# Sheet1.net
KiCad netlist of a schematic drawn in Altium Designer
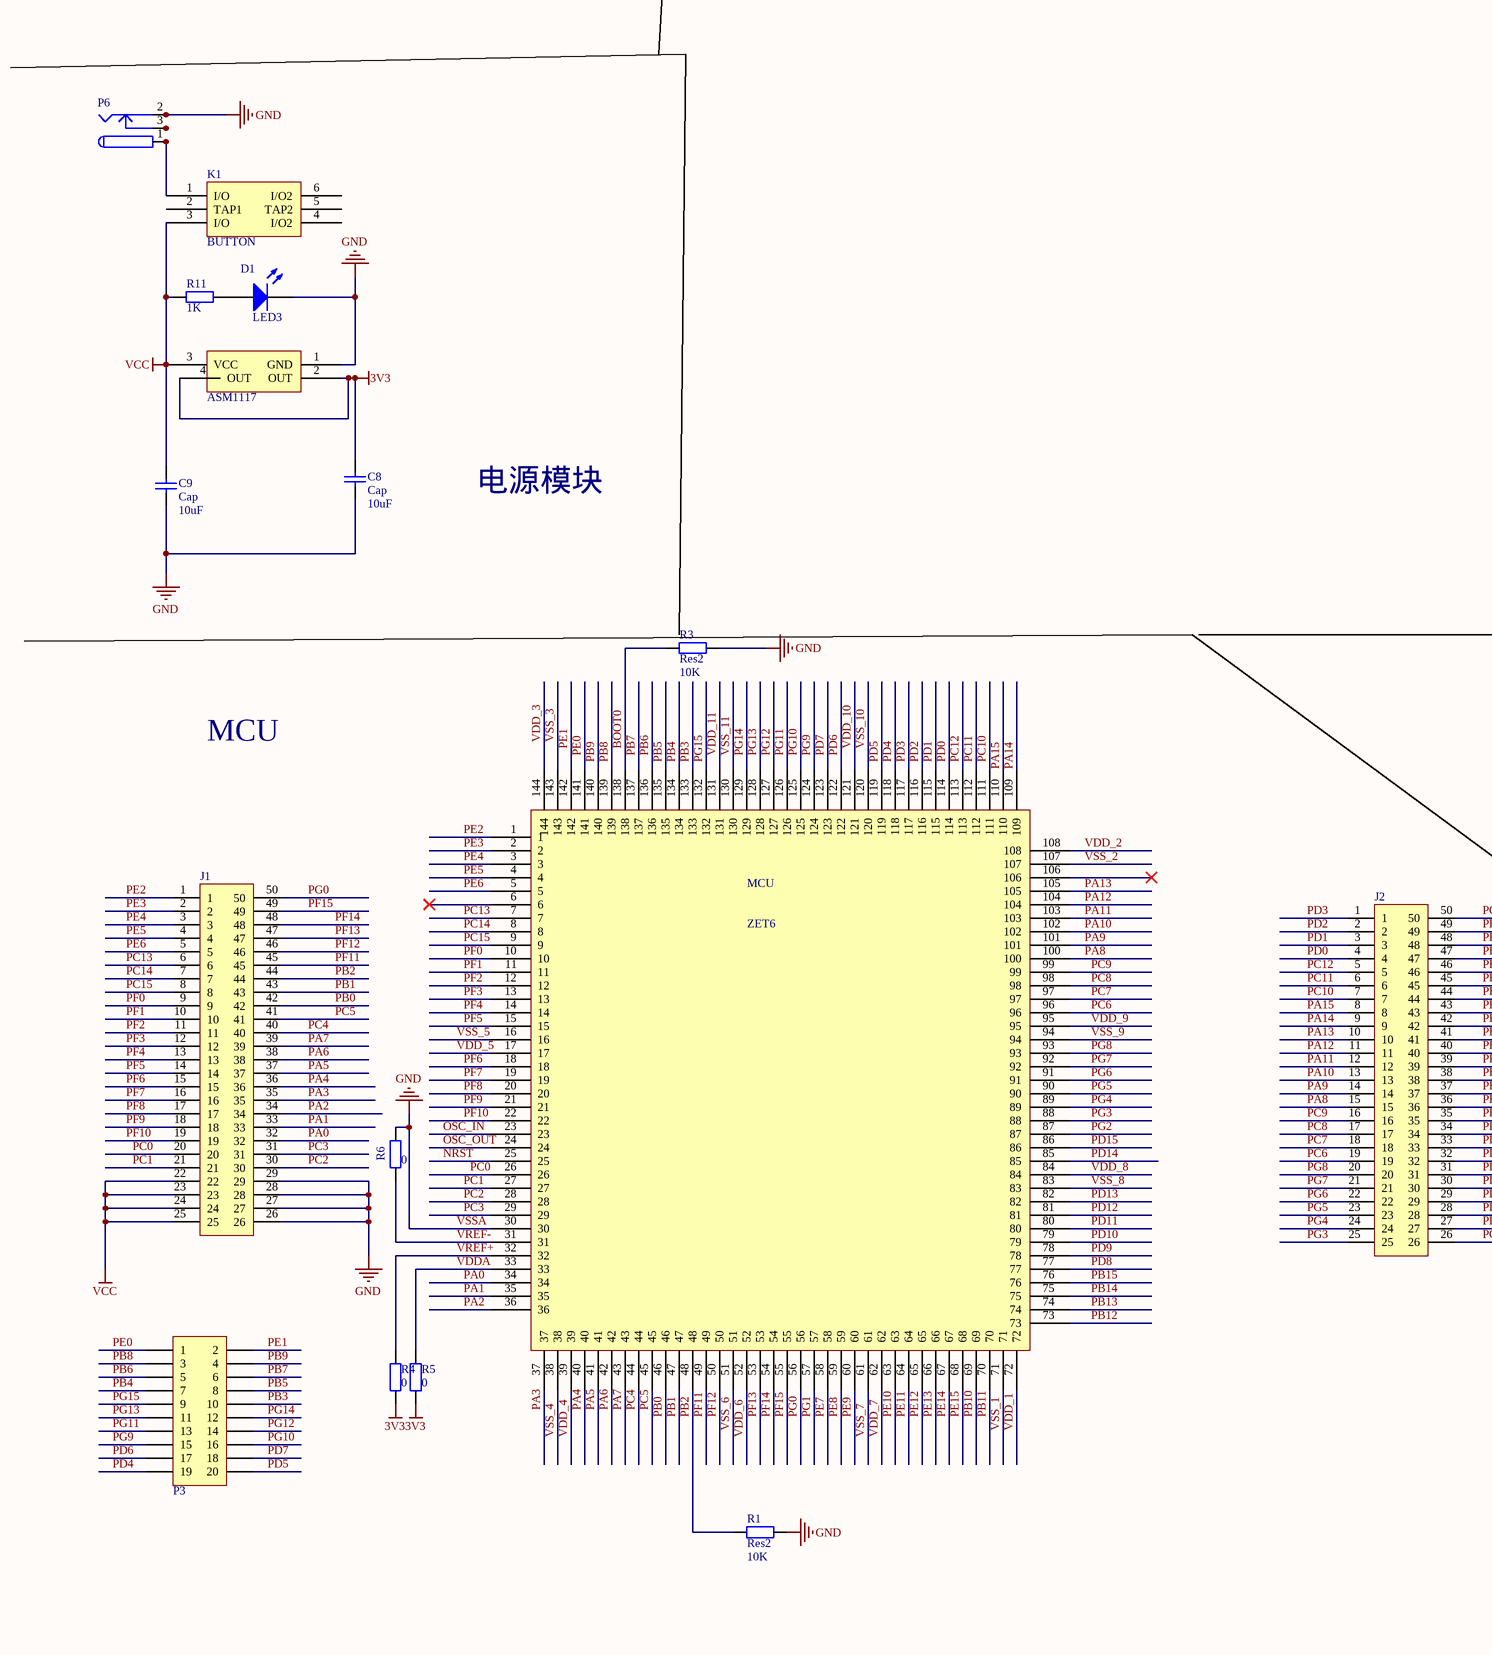
[diagram p0: Sheet1.SchDoc, left]
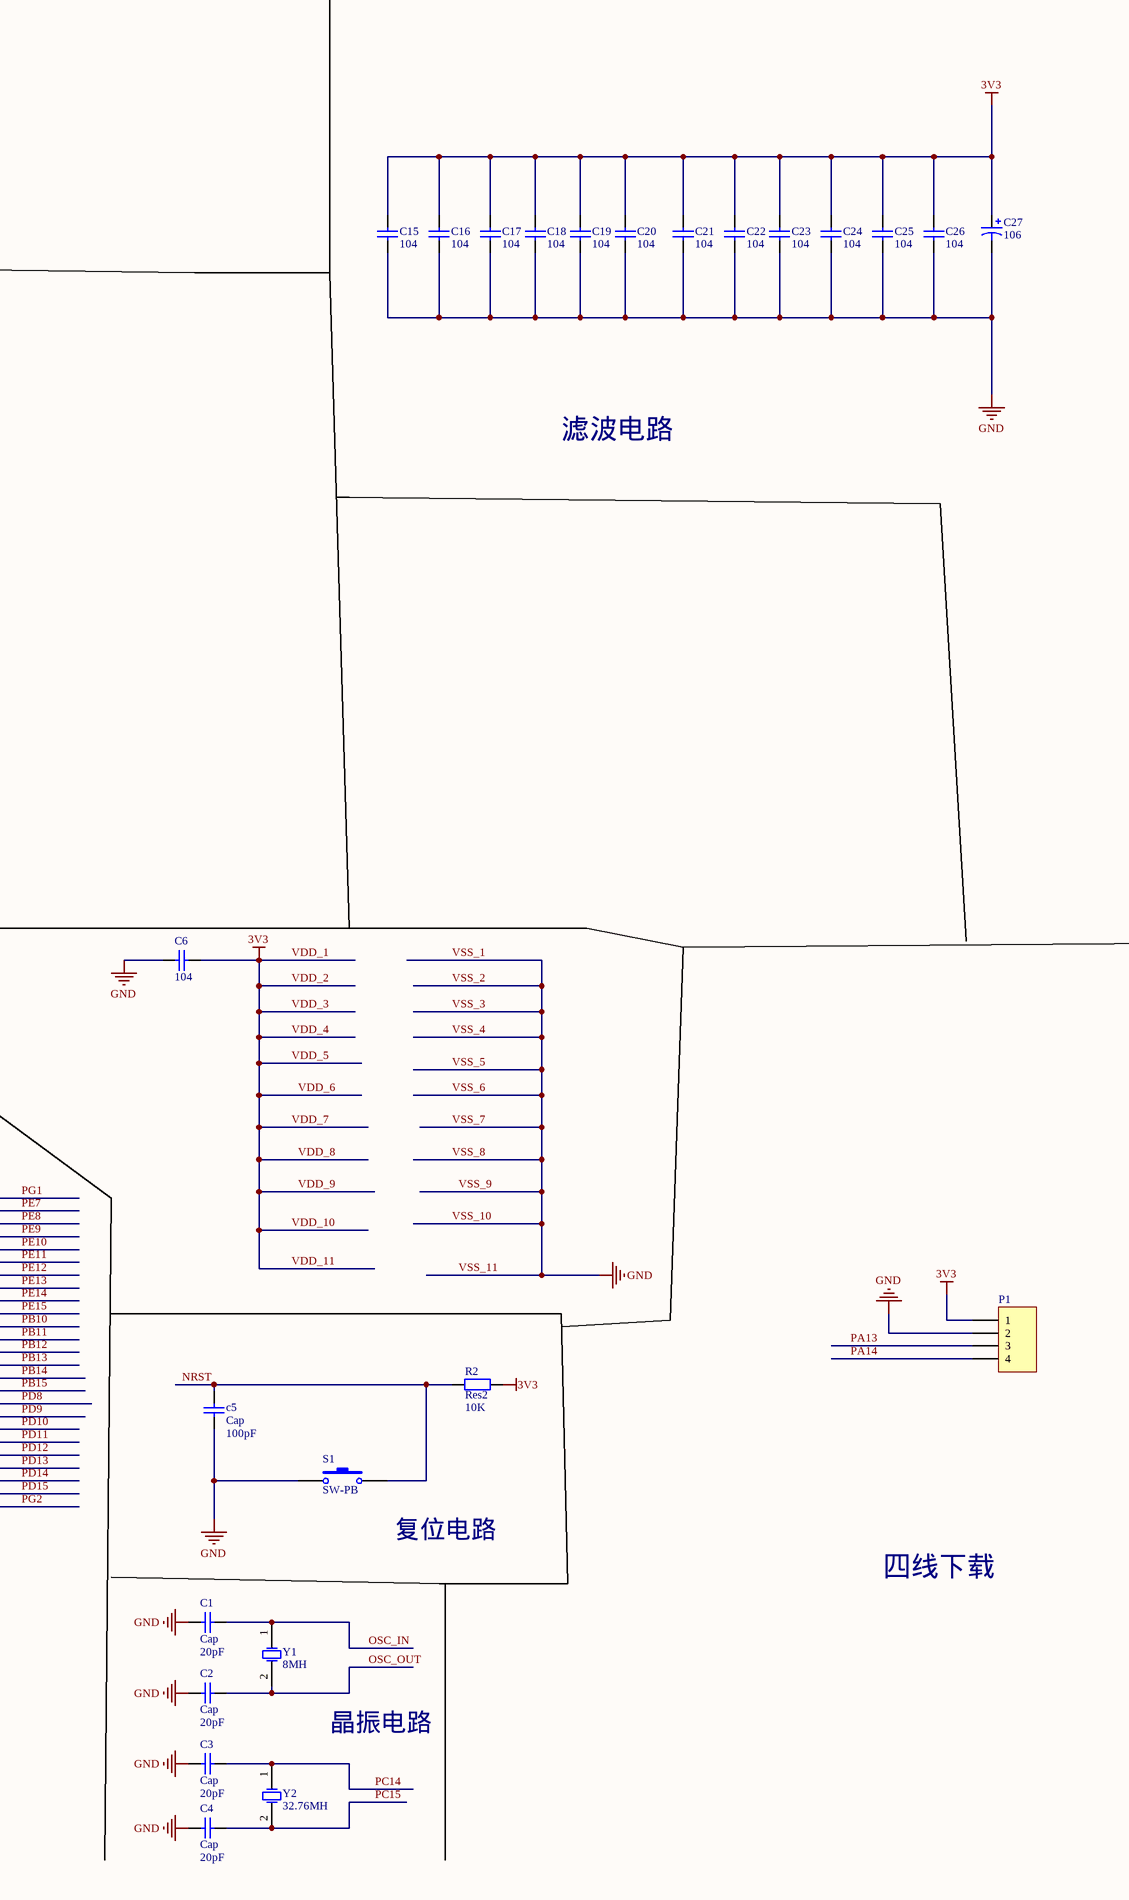
[diagram p1: Sheet1.SchDoc, right]

(export (version "E")
  (design (tool "Eeschema 10.0.6"))
  (components
    (comp (ref "*") (value "ASM1117") (footprint "AMS1117") (libsource (lib "Schlib1") (part "ASM1117")))
    (comp (ref "C1")
      (value "Cap")
      (footprint "0805")
      (description "Capacitor")
      (fields (field (name "ALTIUM_VALUE") "20pF") (field (name "PUBLISHER") "Altium Limited"))
      (libsource (lib "Miscellaneous Devices") (part "Cap"))
    )
    (comp (ref "C2")
      (value "Cap")
      (footprint "0805")
      (description "Capacitor")
      (fields (field (name "ALTIUM_VALUE") "20pF") (field (name "PUBLISHER") "Altium Limited"))
      (libsource (lib "Miscellaneous Devices") (part "Cap"))
    )
    (comp (ref "C3")
      (value "Cap")
      (footprint "0805")
      (description "Capacitor")
      (fields (field (name "ALTIUM_VALUE") "20pF") (field (name "PUBLISHER") "Altium Limited"))
      (libsource (lib "Miscellaneous Devices") (part "Cap"))
    )
    (comp (ref "C4")
      (value "Cap")
      (footprint "0805")
      (description "Capacitor")
      (fields (field (name "ALTIUM_VALUE") "20pF") (field (name "PUBLISHER") "Altium Limited"))
      (libsource (lib "Miscellaneous Devices") (part "Cap"))
    )
    (comp (ref "c5")
      (value "Cap")
      (footprint "0805")
      (description "Capacitor")
      (fields (field (name "ALTIUM_VALUE") "100pF") (field (name "PUBLISHER") "Altium Limited"))
      (libsource (lib "Miscellaneous Devices") (part "Cap"))
    )
    (comp (ref "C6")
      (value "104")
      (footprint "0805")
      (description "Capacitor (Semiconductor SIM Model)")
      (fields (field (name "Comment") "Cap Semi") (field (name "PUBLISHER") "Altium Limited"))
      (libsource (lib "Miscellaneous Devices") (part "Cap Semi"))
    )
    (comp (ref "C8")
      (value "Cap")
      (footprint "0805")
      (description "Capacitor")
      (fields (field (name "ALTIUM_VALUE") "10uF") (field (name "PUBLISHER") "Altium Limited"))
      (libsource (lib "Miscellaneous Devices") (part "Cap"))
    )
    (comp (ref "C9")
      (value "Cap")
      (footprint "0805")
      (description "Capacitor")
      (fields (field (name "ALTIUM_VALUE") "10uF") (field (name "PUBLISHER") "Altium Limited"))
      (libsource (lib "Miscellaneous Devices") (part "Cap"))
    )
    (comp (ref "C15")
      (value "104")
      (footprint "0805")
      (description "Capacitor")
      (fields (field (name "Comment") "Cap") (field (name "PUBLISHER") "Altium Limited"))
      (libsource (lib "Miscellaneous Devices") (part "Cap"))
    )
    (comp (ref "C16")
      (value "104")
      (footprint "0805")
      (description "Capacitor")
      (fields (field (name "Comment") "Cap") (field (name "PUBLISHER") "Altium Limited"))
      (libsource (lib "Miscellaneous Devices") (part "Cap"))
    )
    (comp (ref "C17")
      (value "104")
      (footprint "0805")
      (description "Capacitor")
      (fields (field (name "Comment") "Cap") (field (name "PUBLISHER") "Altium Limited"))
      (libsource (lib "Miscellaneous Devices") (part "Cap"))
    )
    (comp (ref "C18")
      (value "104")
      (footprint "0805")
      (description "Capacitor")
      (fields (field (name "Comment") "Cap") (field (name "PUBLISHER") "Altium Limited"))
      (libsource (lib "Miscellaneous Devices") (part "Cap"))
    )
    (comp (ref "C19")
      (value "104")
      (footprint "0805")
      (description "Capacitor")
      (fields (field (name "Comment") "Cap") (field (name "PUBLISHER") "Altium Limited"))
      (libsource (lib "Miscellaneous Devices") (part "Cap"))
    )
    (comp (ref "C20")
      (value "104")
      (footprint "0805")
      (description "Capacitor")
      (fields (field (name "Comment") "Cap") (field (name "PUBLISHER") "Altium Limited"))
      (libsource (lib "Miscellaneous Devices") (part "Cap"))
    )
    (comp (ref "C21")
      (value "104")
      (footprint "0805")
      (description "Capacitor")
      (fields (field (name "Comment") "Cap") (field (name "PUBLISHER") "Altium Limited"))
      (libsource (lib "Miscellaneous Devices") (part "Cap"))
    )
    (comp (ref "C22")
      (value "104")
      (footprint "0805")
      (description "Capacitor")
      (fields (field (name "Comment") "Cap") (field (name "PUBLISHER") "Altium Limited"))
      (libsource (lib "Miscellaneous Devices") (part "Cap"))
    )
    (comp (ref "C23")
      (value "104")
      (footprint "0805")
      (description "Capacitor")
      (fields (field (name "Comment") "Cap") (field (name "PUBLISHER") "Altium Limited"))
      (libsource (lib "Miscellaneous Devices") (part "Cap"))
    )
    (comp (ref "C24")
      (value "104")
      (footprint "0805")
      (description "Capacitor")
      (fields (field (name "Comment") "Cap") (field (name "PUBLISHER") "Altium Limited"))
      (libsource (lib "Miscellaneous Devices") (part "Cap"))
    )
    (comp (ref "C25")
      (value "104")
      (footprint "0805")
      (description "Capacitor")
      (fields (field (name "Comment") "Cap") (field (name "PUBLISHER") "Altium Limited"))
      (libsource (lib "Miscellaneous Devices") (part "Cap"))
    )
    (comp (ref "C26")
      (value "104")
      (footprint "0805")
      (description "Capacitor")
      (fields (field (name "Comment") "Cap") (field (name "PUBLISHER") "Altium Limited"))
      (libsource (lib "Miscellaneous Devices") (part "Cap"))
    )
    (comp (ref "C27")
      (value "106")
      (footprint "CC6.56.5")
      (description "Polarized Capacitor (Radial)")
      (fields (field (name "Comment") "Cap Pol1") (field (name "PUBLISHER") "Altium Limited"))
      (libsource (lib "Miscellaneous Devices") (part "Cap Pol1"))
    )
    (comp (ref "D1")
      (value "LED3")
      (footprint "RB.1")
      (description "Typical BLUE SiC LED")
      (fields (field (name "PUBLISHER") "Altium Limited"))
      (libsource (lib "Miscellaneous Devices") (part "LED3"))
    )
    (comp (ref "J1")
      (value "Edge Con 50")
      (footprint "HDR2X25")
      (description "50-Pin Edge Connector")
      (fields (field (name "PUBLISHER") "Altium Limited"))
      (libsource (lib "Miscellaneous Connectors") (part "Edge Con 50"))
    )
    (comp (ref "J2")
      (value "Edge Con 50")
      (footprint "HDR2X25")
      (description "50-Pin Edge Connector")
      (fields (field (name "PUBLISHER") "Altium Limited"))
      (libsource (lib "Miscellaneous Connectors") (part "Edge Con 50"))
    )
    (comp (ref "K1") (value "BUTTON") (footprint "BTN8.5*8.5") (libsource (lib "Schlib1") (part "BUTTON")))
    (comp (ref "P1")
      (value "Header 4")
      (footprint "HDR1X4")
      (description "Header, 4-Pin")
      (fields (field (name "PUBLISHER") "Altium Limited"))
      (libsource (lib "Miscellaneous Connectors") (part "Header 4"))
    )
    (comp (ref "P3")
      (value "Header 10X2H")
      (footprint "HDR2X10")
      (description "Header, 10-Pin, Dual row, Right Angle")
      (fields (field (name "PUBLISHER") "Altium Limited"))
      (libsource (lib "Miscellaneous Connectors") (part "Header 10X2H"))
    )
    (comp (ref "P6")
      (value "PWR2.5")
      (footprint "POWER_002")
      (description "Low Voltage Power Supply Connector")
      (fields (field (name "PUBLISHER") "Altium Limited"))
      (libsource (lib "Miscellaneous Connectors") (part "PWR2.5"))
    )
    (comp (ref "R1")
      (value "Res2")
      (footprint "0805")
      (description "Resistor")
      (fields (field (name "ALTIUM_VALUE") "10K") (field (name "PUBLISHER") "Altium Limited"))
      (libsource (lib "Miscellaneous Devices") (part "Res2"))
    )
    (comp (ref "R2")
      (value "Res2")
      (footprint "0805")
      (description "Resistor")
      (fields (field (name "ALTIUM_VALUE") "10K") (field (name "PUBLISHER") "Altium Limited"))
      (libsource (lib "Miscellaneous Devices") (part "Res2"))
    )
    (comp (ref "R3")
      (value "Res2")
      (footprint "0805")
      (description "Resistor")
      (fields (field (name "ALTIUM_VALUE") "10K") (field (name "PUBLISHER") "Altium Limited"))
      (libsource (lib "Miscellaneous Devices") (part "Res2"))
    )
    (comp (ref "R4")
      (value "0")
      (footprint "0805")
      (description "Resistor")
      (fields (field (name "Comment") "Res2") (field (name "PUBLISHER") "Altium Limited"))
      (libsource (lib "") (part "Res2_1"))
    )
    (comp (ref "R5")
      (value "0")
      (footprint "0805")
      (description "Resistor")
      (fields (field (name "Comment") "Res2") (field (name "PUBLISHER") "Altium Limited"))
      (libsource (lib "") (part "Res2_1"))
    )
    (comp (ref "R6")
      (value "0")
      (footprint "0805")
      (description "Resistor")
      (fields (field (name "Comment") "Res2") (field (name "PUBLISHER") "Altium Limited"))
      (libsource (lib "") (part "Res2_1"))
    )
    (comp (ref "R11")
      (value "1K")
      (footprint "0805")
      (description "Resistor")
      (fields (field (name "Comment") "Res2") (field (name "PUBLISHER") "Altium Limited"))
      (libsource (lib "Miscellaneous Devices") (part "Res2"))
    )
    (comp (ref "S1")
      (value "SW-PB")
      (footprint "key4")
      (description "Switch")
      (fields (field (name "PUBLISHER") "Altium Limited"))
      (libsource (lib "Miscellaneous Devices") (part "SW-PB"))
    )
    (comp (ref "Y1")
      (value "8MH")
      (footprint "XTAL_US")
      (description "Crystal Oscillator")
      (fields (field (name "PUBLISHER") "Altium Limited"))
      (libsource (lib "Miscellaneous Devices") (part "XTAL"))
    )
    (comp (ref "Y2")
      (value "32.76MH")
      (footprint "XTAL4")
      (description "Crystal Oscillator")
      (fields (field (name "PUBLISHER") "Altium Limited"))
      (libsource (lib "Miscellaneous Devices") (part "XTAL"))
    )
    (comp (ref "ZET6") (value "MCU") (footprint "LQFP144") (libsource (lib "Schlib1") (part "Component_1")))
  )
  (nets
    (net (code "1") (name "/BOOT0") (class "Default")
      (node (ref "R3") (pin "1") (pinfunction "1_1") (pintype "passive"))
      (node (ref "ZET6") (pin "138") (pinfunction "138_138") (pintype "passive"))
    )
    (net (code "2") (name "/NRST") (class "Default")
      (node (ref "R2") (pin "1") (pinfunction "1_1") (pintype "passive"))
      (node (ref "S1") (pin "2") (pinfunction "2_2") (pintype "passive"))
      (node (ref "ZET6") (pin "25") (pinfunction "25_25") (pintype "passive"))
      (node (ref "c5") (pin "2") (pinfunction "2_2") (pintype "passive"))
    )
    (net (code "3") (name "/OSC_IN") (class "Default")
      (node (ref "C1") (pin "2") (pinfunction "2_2") (pintype "passive"))
      (node (ref "Y1") (pin "1") (pinfunction "OSC1_1") (pintype "passive"))
      (node (ref "ZET6") (pin "23") (pinfunction "23_23") (pintype "passive"))
    )
    (net (code "4") (name "/OSC_OUT") (class "Default")
      (node (ref "C2") (pin "2") (pinfunction "2_2") (pintype "passive"))
      (node (ref "Y1") (pin "2") (pinfunction "OSC2_2") (pintype "passive"))
      (node (ref "ZET6") (pin "24") (pinfunction "24_24") (pintype "passive"))
    )
    (net (code "5") (name "/PA0") (class "Default")
      (node (ref "J1") (pin "32") (pinfunction "32_32") (pintype "passive"))
      (node (ref "ZET6") (pin "34") (pinfunction "34_34") (pintype "passive"))
    )
    (net (code "6") (name "/PA1") (class "Default")
      (node (ref "J1") (pin "33") (pinfunction "33_33") (pintype "passive"))
      (node (ref "ZET6") (pin "35") (pinfunction "35_35") (pintype "passive"))
    )
    (net (code "7") (name "/PA2") (class "Default")
      (node (ref "J1") (pin "34") (pinfunction "34_34") (pintype "passive"))
      (node (ref "ZET6") (pin "36") (pinfunction "36_36") (pintype "passive"))
    )
    (net (code "8") (name "/PA3") (class "Default")
      (node (ref "J1") (pin "35") (pinfunction "35_35") (pintype "passive"))
      (node (ref "ZET6") (pin "37") (pinfunction "37_37") (pintype "passive"))
    )
    (net (code "9") (name "/PA4") (class "Default")
      (node (ref "J1") (pin "36") (pinfunction "36_36") (pintype "passive"))
      (node (ref "ZET6") (pin "40") (pinfunction "40_40") (pintype "passive"))
    )
    (net (code "10") (name "/PA5") (class "Default")
      (node (ref "J1") (pin "37") (pinfunction "37_37") (pintype "passive"))
      (node (ref "ZET6") (pin "41") (pinfunction "41_41") (pintype "passive"))
    )
    (net (code "11") (name "/PA6") (class "Default")
      (node (ref "J1") (pin "38") (pinfunction "38_38") (pintype "passive"))
      (node (ref "ZET6") (pin "42") (pinfunction "42_42") (pintype "passive"))
    )
    (net (code "12") (name "/PA7") (class "Default")
      (node (ref "J1") (pin "39") (pinfunction "39_39") (pintype "passive"))
      (node (ref "ZET6") (pin "43") (pinfunction "43_43") (pintype "passive"))
    )
    (net (code "13") (name "/PA8") (class "Default")
      (node (ref "J2") (pin "15") (pinfunction "15_15") (pintype "passive"))
      (node (ref "ZET6") (pin "100") (pinfunction "100_100") (pintype "passive"))
    )
    (net (code "14") (name "/PA9") (class "Default")
      (node (ref "J2") (pin "14") (pinfunction "14_14") (pintype "passive"))
      (node (ref "ZET6") (pin "101") (pinfunction "101_101") (pintype "passive"))
    )
    (net (code "15") (name "/PA10") (class "Default")
      (node (ref "J2") (pin "13") (pinfunction "13_13") (pintype "passive"))
      (node (ref "ZET6") (pin "102") (pinfunction "102_102") (pintype "passive"))
    )
    (net (code "16") (name "/PA11") (class "Default")
      (node (ref "J2") (pin "12") (pinfunction "12_12") (pintype "passive"))
      (node (ref "ZET6") (pin "103") (pinfunction "103_103") (pintype "passive"))
    )
    (net (code "17") (name "/PA12") (class "Default")
      (node (ref "J2") (pin "11") (pinfunction "11_11") (pintype "passive"))
      (node (ref "ZET6") (pin "104") (pinfunction "104_104") (pintype "passive"))
    )
    (net (code "18") (name "/PA13") (class "Default")
      (node (ref "J2") (pin "10") (pinfunction "10_10") (pintype "passive"))
      (node (ref "P1") (pin "3") (pinfunction "3_3") (pintype "passive"))
      (node (ref "ZET6") (pin "105") (pinfunction "105_105") (pintype "passive"))
    )
    (net (code "19") (name "/PA14") (class "Default")
      (node (ref "J2") (pin "9") (pinfunction "9_9") (pintype "passive"))
      (node (ref "P1") (pin "4") (pinfunction "4_4") (pintype "passive"))
      (node (ref "ZET6") (pin "109") (pinfunction "109_109") (pintype "passive"))
    )
    (net (code "20") (name "/PA15") (class "Default")
      (node (ref "J2") (pin "8") (pinfunction "8_8") (pintype "passive"))
      (node (ref "ZET6") (pin "110") (pinfunction "110_110") (pintype "passive"))
    )
    (net (code "21") (name "/PB0") (class "Default")
      (node (ref "J1") (pin "42") (pinfunction "42_42") (pintype "passive"))
      (node (ref "ZET6") (pin "46") (pinfunction "46_46") (pintype "passive"))
    )
    (net (code "22") (name "/PB1") (class "Default")
      (node (ref "J1") (pin "43") (pinfunction "43_43") (pintype "passive"))
      (node (ref "ZET6") (pin "47") (pinfunction "47_47") (pintype "passive"))
    )
    (net (code "23") (name "/PB2") (class "Default")
      (node (ref "J1") (pin "44") (pinfunction "44_44") (pintype "passive"))
      (node (ref "R1") (pin "1") (pinfunction "1_1") (pintype "passive"))
      (node (ref "ZET6") (pin "48") (pinfunction "48_48") (pintype "passive"))
    )
    (net (code "24") (name "/PB3") (class "Default")
      (node (ref "P3") (pin "10") (pinfunction "10_10") (pintype "passive"))
      (node (ref "ZET6") (pin "133") (pinfunction "133_133") (pintype "passive"))
    )
    (net (code "25") (name "/PB4") (class "Default")
      (node (ref "P3") (pin "7") (pinfunction "7_7") (pintype "passive"))
      (node (ref "ZET6") (pin "134") (pinfunction "134_134") (pintype "passive"))
    )
    (net (code "26") (name "/PB5") (class "Default")
      (node (ref "P3") (pin "8") (pinfunction "8_8") (pintype "passive"))
      (node (ref "ZET6") (pin "135") (pinfunction "135_135") (pintype "passive"))
    )
    (net (code "27") (name "/PB6") (class "Default")
      (node (ref "P3") (pin "5") (pinfunction "5_5") (pintype "passive"))
      (node (ref "ZET6") (pin "136") (pinfunction "136_136") (pintype "passive"))
    )
    (net (code "28") (name "/PB7") (class "Default")
      (node (ref "P3") (pin "6") (pinfunction "6_6") (pintype "passive"))
      (node (ref "ZET6") (pin "137") (pinfunction "137_137") (pintype "passive"))
    )
    (net (code "29") (name "/PB8") (class "Default")
      (node (ref "P3") (pin "3") (pinfunction "3_3") (pintype "passive"))
      (node (ref "ZET6") (pin "139") (pinfunction "139_139") (pintype "passive"))
    )
    (net (code "30") (name "/PB9") (class "Default")
      (node (ref "P3") (pin "4") (pinfunction "4_4") (pintype "passive"))
      (node (ref "ZET6") (pin "140") (pinfunction "140_140") (pintype "passive"))
    )
    (net (code "31") (name "/PB10") (class "Default")
      (node (ref "J2") (pin "40") (pinfunction "40_40") (pintype "passive"))
      (node (ref "ZET6") (pin "69") (pinfunction "69_69") (pintype "passive"))
    )
    (net (code "32") (name "/PB11") (class "Default")
      (node (ref "J2") (pin "39") (pinfunction "39_39") (pintype "passive"))
      (node (ref "ZET6") (pin "70") (pinfunction "70_70") (pintype "passive"))
    )
    (net (code "33") (name "/PB12") (class "Default")
      (node (ref "J2") (pin "38") (pinfunction "38_38") (pintype "passive"))
      (node (ref "ZET6") (pin "73") (pinfunction "73_73") (pintype "passive"))
    )
    (net (code "34") (name "/PB13") (class "Default")
      (node (ref "J2") (pin "37") (pinfunction "37_37") (pintype "passive"))
      (node (ref "ZET6") (pin "74") (pinfunction "74_74") (pintype "passive"))
    )
    (net (code "35") (name "/PB14") (class "Default")
      (node (ref "J2") (pin "36") (pinfunction "36_36") (pintype "passive"))
      (node (ref "ZET6") (pin "75") (pinfunction "75_75") (pintype "passive"))
    )
    (net (code "36") (name "/PB15") (class "Default")
      (node (ref "J2") (pin "35") (pinfunction "35_35") (pintype "passive"))
      (node (ref "ZET6") (pin "76") (pinfunction "76_76") (pintype "passive"))
    )
    (net (code "37") (name "/PC0") (class "Default")
      (node (ref "J1") (pin "20") (pinfunction "20_20") (pintype "passive"))
      (node (ref "ZET6") (pin "26") (pinfunction "26_26") (pintype "passive"))
    )
    (net (code "38") (name "/PC1") (class "Default")
      (node (ref "J1") (pin "21") (pinfunction "21_21") (pintype "passive"))
      (node (ref "ZET6") (pin "27") (pinfunction "27_27") (pintype "passive"))
    )
    (net (code "39") (name "/PC2") (class "Default")
      (node (ref "J1") (pin "30") (pinfunction "30_30") (pintype "passive"))
      (node (ref "ZET6") (pin "28") (pinfunction "28_28") (pintype "passive"))
    )
    (net (code "40") (name "/PC3") (class "Default")
      (node (ref "J1") (pin "31") (pinfunction "31_31") (pintype "passive"))
      (node (ref "ZET6") (pin "29") (pinfunction "29_29") (pintype "passive"))
    )
    (net (code "41") (name "/PC4") (class "Default")
      (node (ref "J1") (pin "40") (pinfunction "40_40") (pintype "passive"))
      (node (ref "ZET6") (pin "44") (pinfunction "44_44") (pintype "passive"))
    )
    (net (code "42") (name "/PC5") (class "Default")
      (node (ref "J1") (pin "41") (pinfunction "41_41") (pintype "passive"))
      (node (ref "ZET6") (pin "45") (pinfunction "45_45") (pintype "passive"))
    )
    (net (code "43") (name "/PC6") (class "Default")
      (node (ref "J2") (pin "19") (pinfunction "19_19") (pintype "passive"))
      (node (ref "ZET6") (pin "96") (pinfunction "96_96") (pintype "passive"))
    )
    (net (code "44") (name "/PC7") (class "Default")
      (node (ref "J2") (pin "18") (pinfunction "18_18") (pintype "passive"))
      (node (ref "ZET6") (pin "97") (pinfunction "97_97") (pintype "passive"))
    )
    (net (code "45") (name "/PC8") (class "Default")
      (node (ref "J2") (pin "17") (pinfunction "17_17") (pintype "passive"))
      (node (ref "ZET6") (pin "98") (pinfunction "98_98") (pintype "passive"))
    )
    (net (code "46") (name "/PC9") (class "Default")
      (node (ref "J2") (pin "16") (pinfunction "16_16") (pintype "passive"))
      (node (ref "ZET6") (pin "99") (pinfunction "99_99") (pintype "passive"))
    )
    (net (code "47") (name "/PC10") (class "Default")
      (node (ref "J2") (pin "7") (pinfunction "7_7") (pintype "passive"))
      (node (ref "ZET6") (pin "111") (pinfunction "111_111") (pintype "passive"))
    )
    (net (code "48") (name "/PC11") (class "Default")
      (node (ref "J2") (pin "6") (pinfunction "6_6") (pintype "passive"))
      (node (ref "ZET6") (pin "112") (pinfunction "112_112") (pintype "passive"))
    )
    (net (code "49") (name "/PC12") (class "Default")
      (node (ref "J2") (pin "5") (pinfunction "5_5") (pintype "passive"))
      (node (ref "ZET6") (pin "113") (pinfunction "113_113") (pintype "passive"))
    )
    (net (code "50") (name "/PC13") (class "Default")
      (node (ref "J1") (pin "6") (pinfunction "6_6") (pintype "passive"))
      (node (ref "ZET6") (pin "7") (pinfunction "7_7") (pintype "passive"))
    )
    (net (code "51") (name "/PC14") (class "Default")
      (node (ref "C3") (pin "2") (pinfunction "2_2") (pintype "passive"))
      (node (ref "J1") (pin "7") (pinfunction "7_7") (pintype "passive"))
      (node (ref "Y2") (pin "1") (pinfunction "OSC1_1") (pintype "passive"))
      (node (ref "ZET6") (pin "8") (pinfunction "8_8") (pintype "passive"))
    )
    (net (code "52") (name "/PC15") (class "Default")
      (node (ref "C4") (pin "2") (pinfunction "2_2") (pintype "passive"))
      (node (ref "J1") (pin "8") (pinfunction "8_8") (pintype "passive"))
      (node (ref "Y2") (pin "2") (pinfunction "OSC2_2") (pintype "passive"))
      (node (ref "ZET6") (pin "9") (pinfunction "9_9") (pintype "passive"))
    )
    (net (code "53") (name "/PD0") (class "Default")
      (node (ref "J2") (pin "4") (pinfunction "4_4") (pintype "passive"))
      (node (ref "ZET6") (pin "114") (pinfunction "114_114") (pintype "passive"))
    )
    (net (code "54") (name "/PD1") (class "Default")
      (node (ref "J2") (pin "3") (pinfunction "3_3") (pintype "passive"))
      (node (ref "ZET6") (pin "115") (pinfunction "115_115") (pintype "passive"))
    )
    (net (code "55") (name "/PD2") (class "Default")
      (node (ref "J2") (pin "2") (pinfunction "2_2") (pintype "passive"))
      (node (ref "ZET6") (pin "116") (pinfunction "116_116") (pintype "passive"))
    )
    (net (code "56") (name "/PD3") (class "Default")
      (node (ref "J2") (pin "1") (pinfunction "1_1") (pintype "passive"))
      (node (ref "ZET6") (pin "117") (pinfunction "117_117") (pintype "passive"))
    )
    (net (code "57") (name "/PD4") (class "Default")
      (node (ref "P3") (pin "19") (pinfunction "19_19") (pintype "passive"))
      (node (ref "ZET6") (pin "118") (pinfunction "118_118") (pintype "passive"))
    )
    (net (code "58") (name "/PD5") (class "Default")
      (node (ref "P3") (pin "20") (pinfunction "20_20") (pintype "passive"))
      (node (ref "ZET6") (pin "119") (pinfunction "119_119") (pintype "passive"))
    )
    (net (code "59") (name "/PD6") (class "Default")
      (node (ref "P3") (pin "17") (pinfunction "17_17") (pintype "passive"))
      (node (ref "ZET6") (pin "122") (pinfunction "122_122") (pintype "passive"))
    )
    (net (code "60") (name "/PD7") (class "Default")
      (node (ref "P3") (pin "18") (pinfunction "18_18") (pintype "passive"))
      (node (ref "ZET6") (pin "123") (pinfunction "123_123") (pintype "passive"))
    )
    (net (code "61") (name "/PD8") (class "Default")
      (node (ref "J2") (pin "34") (pinfunction "34_34") (pintype "passive"))
      (node (ref "ZET6") (pin "77") (pinfunction "77_77") (pintype "passive"))
    )
    (net (code "62") (name "/PD9") (class "Default")
      (node (ref "J2") (pin "33") (pinfunction "33_33") (pintype "passive"))
      (node (ref "ZET6") (pin "78") (pinfunction "78_78") (pintype "passive"))
    )
    (net (code "63") (name "/PD10") (class "Default")
      (node (ref "J2") (pin "32") (pinfunction "32_32") (pintype "passive"))
      (node (ref "ZET6") (pin "79") (pinfunction "79_79") (pintype "passive"))
    )
    (net (code "64") (name "/PD11") (class "Default")
      (node (ref "J2") (pin "31") (pinfunction "31_31") (pintype "passive"))
      (node (ref "ZET6") (pin "80") (pinfunction "80_80") (pintype "passive"))
    )
    (net (code "65") (name "/PD12") (class "Default")
      (node (ref "J2") (pin "30") (pinfunction "30_30") (pintype "passive"))
      (node (ref "ZET6") (pin "81") (pinfunction "81_81") (pintype "passive"))
    )
    (net (code "66") (name "/PD13") (class "Default")
      (node (ref "J2") (pin "29") (pinfunction "29_29") (pintype "passive"))
      (node (ref "ZET6") (pin "82") (pinfunction "82_82") (pintype "passive"))
    )
    (net (code "67") (name "/PD14") (class "Default")
      (node (ref "J2") (pin "28") (pinfunction "28_28") (pintype "passive"))
      (node (ref "ZET6") (pin "85") (pinfunction "85_85") (pintype "passive"))
    )
    (net (code "68") (name "/PD15") (class "Default")
      (node (ref "J2") (pin "27") (pinfunction "27_27") (pintype "passive"))
      (node (ref "ZET6") (pin "86") (pinfunction "86_86") (pintype "passive"))
    )
    (net (code "69") (name "/PE0") (class "Default")
      (node (ref "P3") (pin "1") (pinfunction "1_1") (pintype "passive"))
      (node (ref "ZET6") (pin "141") (pinfunction "141_141") (pintype "passive"))
    )
    (net (code "70") (name "/PE1") (class "Default")
      (node (ref "P3") (pin "2") (pinfunction "2_2") (pintype "passive"))
      (node (ref "ZET6") (pin "142") (pinfunction "142_142") (pintype "passive"))
    )
    (net (code "71") (name "/PE2") (class "Default")
      (node (ref "J1") (pin "1") (pinfunction "1_1") (pintype "passive"))
      (node (ref "ZET6") (pin "1") (pinfunction "1_1") (pintype "passive"))
    )
    (net (code "72") (name "/PE3") (class "Default")
      (node (ref "J1") (pin "2") (pinfunction "2_2") (pintype "passive"))
      (node (ref "ZET6") (pin "2") (pinfunction "2_2") (pintype "passive"))
    )
    (net (code "73") (name "/PE4") (class "Default")
      (node (ref "J1") (pin "3") (pinfunction "3_3") (pintype "passive"))
      (node (ref "ZET6") (pin "3") (pinfunction "3_3") (pintype "passive"))
    )
    (net (code "74") (name "/PE5") (class "Default")
      (node (ref "J1") (pin "4") (pinfunction "4_4") (pintype "passive"))
      (node (ref "ZET6") (pin "4") (pinfunction "4_4") (pintype "passive"))
    )
    (net (code "75") (name "/PE6") (class "Default")
      (node (ref "J1") (pin "5") (pinfunction "5_5") (pintype "passive"))
      (node (ref "ZET6") (pin "5") (pinfunction "5_5") (pintype "passive"))
    )
    (net (code "76") (name "/PE7") (class "Default")
      (node (ref "J2") (pin "49") (pinfunction "49_49") (pintype "passive"))
      (node (ref "ZET6") (pin "58") (pinfunction "58_58") (pintype "passive"))
    )
    (net (code "77") (name "/PE8") (class "Default")
      (node (ref "J2") (pin "48") (pinfunction "48_48") (pintype "passive"))
      (node (ref "ZET6") (pin "59") (pinfunction "59_59") (pintype "passive"))
    )
    (net (code "78") (name "/PE9") (class "Default")
      (node (ref "J2") (pin "47") (pinfunction "47_47") (pintype "passive"))
      (node (ref "ZET6") (pin "60") (pinfunction "60_60") (pintype "passive"))
    )
    (net (code "79") (name "/PE10") (class "Default")
      (node (ref "J2") (pin "46") (pinfunction "46_46") (pintype "passive"))
      (node (ref "ZET6") (pin "63") (pinfunction "63_63") (pintype "passive"))
    )
    (net (code "80") (name "/PE11") (class "Default")
      (node (ref "J2") (pin "45") (pinfunction "45_45") (pintype "passive"))
      (node (ref "ZET6") (pin "64") (pinfunction "64_64") (pintype "passive"))
    )
    (net (code "81") (name "/PE12") (class "Default")
      (node (ref "J2") (pin "44") (pinfunction "44_44") (pintype "passive"))
      (node (ref "ZET6") (pin "65") (pinfunction "65_65") (pintype "passive"))
    )
    (net (code "82") (name "/PE13") (class "Default")
      (node (ref "J2") (pin "43") (pinfunction "43_43") (pintype "passive"))
      (node (ref "ZET6") (pin "66") (pinfunction "66_66") (pintype "passive"))
    )
    (net (code "83") (name "/PE14") (class "Default")
      (node (ref "J2") (pin "42") (pinfunction "42_42") (pintype "passive"))
      (node (ref "ZET6") (pin "67") (pinfunction "67_67") (pintype "passive"))
    )
    (net (code "84") (name "/PE15") (class "Default")
      (node (ref "J2") (pin "41") (pinfunction "41_41") (pintype "passive"))
      (node (ref "ZET6") (pin "68") (pinfunction "68_68") (pintype "passive"))
    )
    (net (code "85") (name "/PF0") (class "Default")
      (node (ref "J1") (pin "9") (pinfunction "9_9") (pintype "passive"))
      (node (ref "ZET6") (pin "10") (pinfunction "10_10") (pintype "passive"))
    )
    (net (code "86") (name "/PF1") (class "Default")
      (node (ref "J1") (pin "10") (pinfunction "10_10") (pintype "passive"))
      (node (ref "ZET6") (pin "11") (pinfunction "11_11") (pintype "passive"))
    )
    (net (code "87") (name "/PF2") (class "Default")
      (node (ref "J1") (pin "11") (pinfunction "11_11") (pintype "passive"))
      (node (ref "ZET6") (pin "12") (pinfunction "12_12") (pintype "passive"))
    )
    (net (code "88") (name "/PF3") (class "Default")
      (node (ref "J1") (pin "12") (pinfunction "12_12") (pintype "passive"))
      (node (ref "ZET6") (pin "13") (pinfunction "13_13") (pintype "passive"))
    )
    (net (code "89") (name "/PF4") (class "Default")
      (node (ref "J1") (pin "13") (pinfunction "13_13") (pintype "passive"))
      (node (ref "ZET6") (pin "14") (pinfunction "14_14") (pintype "passive"))
    )
    (net (code "90") (name "/PF5") (class "Default")
      (node (ref "J1") (pin "14") (pinfunction "14_14") (pintype "passive"))
      (node (ref "ZET6") (pin "15") (pinfunction "15_15") (pintype "passive"))
    )
    (net (code "91") (name "/PF6") (class "Default")
      (node (ref "J1") (pin "15") (pinfunction "15_15") (pintype "passive"))
      (node (ref "ZET6") (pin "18") (pinfunction "18_18") (pintype "passive"))
    )
    (net (code "92") (name "/PF7") (class "Default")
      (node (ref "J1") (pin "16") (pinfunction "16_16") (pintype "passive"))
      (node (ref "ZET6") (pin "19") (pinfunction "19_19") (pintype "passive"))
    )
    (net (code "93") (name "/PF8") (class "Default")
      (node (ref "J1") (pin "17") (pinfunction "17_17") (pintype "passive"))
      (node (ref "ZET6") (pin "20") (pinfunction "20_20") (pintype "passive"))
    )
    (net (code "94") (name "/PF9") (class "Default")
      (node (ref "J1") (pin "18") (pinfunction "18_18") (pintype "passive"))
      (node (ref "ZET6") (pin "21") (pinfunction "21_21") (pintype "passive"))
    )
    (net (code "95") (name "/PF10") (class "Default")
      (node (ref "J1") (pin "19") (pinfunction "19_19") (pintype "passive"))
      (node (ref "ZET6") (pin "22") (pinfunction "22_22") (pintype "passive"))
    )
    (net (code "96") (name "/PF11") (class "Default")
      (node (ref "J1") (pin "45") (pinfunction "45_45") (pintype "passive"))
      (node (ref "ZET6") (pin "49") (pinfunction "49_49") (pintype "passive"))
    )
    (net (code "97") (name "/PF12") (class "Default")
      (node (ref "J1") (pin "46") (pinfunction "46_46") (pintype "passive"))
      (node (ref "ZET6") (pin "50") (pinfunction "50_50") (pintype "passive"))
    )
    (net (code "98") (name "/PF13") (class "Default")
      (node (ref "J1") (pin "47") (pinfunction "47_47") (pintype "passive"))
      (node (ref "ZET6") (pin "53") (pinfunction "53_53") (pintype "passive"))
    )
    (net (code "99") (name "/PF14") (class "Default")
      (node (ref "J1") (pin "48") (pinfunction "48_48") (pintype "passive"))
      (node (ref "ZET6") (pin "54") (pinfunction "54_54") (pintype "passive"))
    )
    (net (code "100") (name "/PF15") (class "Default")
      (node (ref "J1") (pin "49") (pinfunction "49_49") (pintype "passive"))
      (node (ref "ZET6") (pin "55") (pinfunction "55_55") (pintype "passive"))
    )
    (net (code "101") (name "/PG0") (class "Default")
      (node (ref "J1") (pin "50") (pinfunction "50_50") (pintype "passive"))
      (node (ref "ZET6") (pin "56") (pinfunction "56_56") (pintype "passive"))
    )
    (net (code "102") (name "/PG1") (class "Default")
      (node (ref "J2") (pin "50") (pinfunction "50_50") (pintype "passive"))
      (node (ref "ZET6") (pin "57") (pinfunction "57_57") (pintype "passive"))
    )
    (net (code "103") (name "/PG2") (class "Default")
      (node (ref "J2") (pin "26") (pinfunction "26_26") (pintype "passive"))
      (node (ref "ZET6") (pin "87") (pinfunction "87_87") (pintype "passive"))
    )
    (net (code "104") (name "/PG3") (class "Default")
      (node (ref "J2") (pin "25") (pinfunction "25_25") (pintype "passive"))
      (node (ref "ZET6") (pin "88") (pinfunction "88_88") (pintype "passive"))
    )
    (net (code "105") (name "/PG4") (class "Default")
      (node (ref "J2") (pin "24") (pinfunction "24_24") (pintype "passive"))
      (node (ref "ZET6") (pin "89") (pinfunction "89_89") (pintype "passive"))
    )
    (net (code "106") (name "/PG5") (class "Default")
      (node (ref "J2") (pin "23") (pinfunction "23_23") (pintype "passive"))
      (node (ref "ZET6") (pin "90") (pinfunction "90_90") (pintype "passive"))
    )
    (net (code "107") (name "/PG6") (class "Default")
      (node (ref "J2") (pin "22") (pinfunction "22_22") (pintype "passive"))
      (node (ref "ZET6") (pin "91") (pinfunction "91_91") (pintype "passive"))
    )
    (net (code "108") (name "/PG7") (class "Default")
      (node (ref "J2") (pin "21") (pinfunction "21_21") (pintype "passive"))
      (node (ref "ZET6") (pin "92") (pinfunction "92_92") (pintype "passive"))
    )
    (net (code "109") (name "/PG8") (class "Default")
      (node (ref "J2") (pin "20") (pinfunction "20_20") (pintype "passive"))
      (node (ref "ZET6") (pin "93") (pinfunction "93_93") (pintype "passive"))
    )
    (net (code "110") (name "/PG9") (class "Default")
      (node (ref "P3") (pin "15") (pinfunction "15_15") (pintype "passive"))
      (node (ref "ZET6") (pin "124") (pinfunction "124_124") (pintype "passive"))
    )
    (net (code "111") (name "/PG10") (class "Default")
      (node (ref "P3") (pin "16") (pinfunction "16_16") (pintype "passive"))
      (node (ref "ZET6") (pin "125") (pinfunction "125_125") (pintype "passive"))
    )
    (net (code "112") (name "/PG11") (class "Default")
      (node (ref "P3") (pin "13") (pinfunction "13_13") (pintype "passive"))
      (node (ref "ZET6") (pin "126") (pinfunction "126_126") (pintype "passive"))
    )
    (net (code "113") (name "/PG12") (class "Default")
      (node (ref "P3") (pin "14") (pinfunction "14_14") (pintype "passive"))
      (node (ref "ZET6") (pin "127") (pinfunction "127_127") (pintype "passive"))
    )
    (net (code "114") (name "/PG13") (class "Default")
      (node (ref "P3") (pin "11") (pinfunction "11_11") (pintype "passive"))
      (node (ref "ZET6") (pin "128") (pinfunction "128_128") (pintype "passive"))
    )
    (net (code "115") (name "/PG14") (class "Default")
      (node (ref "P3") (pin "12") (pinfunction "12_12") (pintype "passive"))
      (node (ref "ZET6") (pin "129") (pinfunction "129_129") (pintype "passive"))
    )
    (net (code "116") (name "/PG15") (class "Default")
      (node (ref "P3") (pin "9") (pinfunction "9_9") (pintype "passive"))
      (node (ref "ZET6") (pin "132") (pinfunction "132_132") (pintype "passive"))
    )
    (net (code "117") (name "/VDDA") (class "Default")
      (node (ref "R5") (pin "2") (pinfunction "2_2") (pintype "passive"))
      (node (ref "ZET6") (pin "33") (pinfunction "33_33") (pintype "passive"))
    )
    (net (code "118") (name "/VREF+") (class "Default")
      (node (ref "R4") (pin "2") (pinfunction "2_2") (pintype "passive"))
      (node (ref "ZET6") (pin "32") (pinfunction "32_32") (pintype "passive"))
    )
    (net (code "119") (name "/VREF-") (class "Default")
      (node (ref "R6") (pin "1") (pinfunction "1_1") (pintype "passive"))
      (node (ref "ZET6") (pin "31") (pinfunction "31_31") (pintype "passive"))
    )
    (net (code "120") (name "3V3") (class "Default")
      (node (ref "*") (pin "2") (pinfunction "OUT_2") (pintype "passive"))
      (node (ref "*") (pin "4") (pinfunction "OUT_4") (pintype "passive"))
      (node (ref "C15") (pin "2") (pinfunction "2_2") (pintype "passive"))
      (node (ref "C16") (pin "2") (pinfunction "2_2") (pintype "passive"))
      (node (ref "C17") (pin "1") (pinfunction "1_1") (pintype "passive"))
      (node (ref "C18") (pin "2") (pinfunction "2_2") (pintype "passive"))
      (node (ref "C19") (pin "2") (pinfunction "2_2") (pintype "passive"))
      (node (ref "C20") (pin "2") (pinfunction "2_2") (pintype "passive"))
      (node (ref "C21") (pin "2") (pinfunction "2_2") (pintype "passive"))
      (node (ref "C22") (pin "2") (pinfunction "2_2") (pintype "passive"))
      (node (ref "C23") (pin "2") (pinfunction "2_2") (pintype "passive"))
      (node (ref "C24") (pin "2") (pinfunction "2_2") (pintype "passive"))
      (node (ref "C25") (pin "2") (pinfunction "2_2") (pintype "passive"))
      (node (ref "C26") (pin "2") (pinfunction "2_2") (pintype "passive"))
      (node (ref "C27") (pin "1") (pinfunction "1_1") (pintype "passive"))
      (node (ref "C6") (pin "2") (pinfunction "2_2") (pintype "passive"))
      (node (ref "C8") (pin "2") (pinfunction "2_2") (pintype "passive"))
      (node (ref "P1") (pin "1") (pinfunction "1_1") (pintype "passive"))
      (node (ref "R2") (pin "2") (pinfunction "2_2") (pintype "passive"))
      (node (ref "R4") (pin "1") (pinfunction "1_1") (pintype "passive"))
      (node (ref "R5") (pin "1") (pinfunction "1_1") (pintype "passive"))
      (node (ref "ZET6") (pin "108") (pinfunction "108_108") (pintype "passive"))
      (node (ref "ZET6") (pin "121") (pinfunction "121_121") (pintype "passive"))
      (node (ref "ZET6") (pin "131") (pinfunction "131_131") (pintype "passive"))
      (node (ref "ZET6") (pin "144") (pinfunction "144_144") (pintype "passive"))
      (node (ref "ZET6") (pin "17") (pinfunction "17_17") (pintype "passive"))
      (node (ref "ZET6") (pin "39") (pinfunction "39_39") (pintype "passive"))
      (node (ref "ZET6") (pin "52") (pinfunction "52_52") (pintype "passive"))
      (node (ref "ZET6") (pin "62") (pinfunction "62_62") (pintype "passive"))
      (node (ref "ZET6") (pin "72") (pinfunction "72_72") (pintype "passive"))
      (node (ref "ZET6") (pin "84") (pinfunction "84_84") (pintype "passive"))
      (node (ref "ZET6") (pin "95") (pinfunction "95_95") (pintype "passive"))
    )
    (net (code "121") (name "GND") (class "Default")
      (node (ref "*") (pin "1") (pinfunction "GND_1") (pintype "passive"))
      (node (ref "C1") (pin "1") (pinfunction "1_1") (pintype "passive"))
      (node (ref "C15") (pin "1") (pinfunction "1_1") (pintype "passive"))
      (node (ref "C16") (pin "1") (pinfunction "1_1") (pintype "passive"))
      (node (ref "C17") (pin "2") (pinfunction "2_2") (pintype "passive"))
      (node (ref "C18") (pin "1") (pinfunction "1_1") (pintype "passive"))
      (node (ref "C19") (pin "1") (pinfunction "1_1") (pintype "passive"))
      (node (ref "C2") (pin "1") (pinfunction "1_1") (pintype "passive"))
      (node (ref "C20") (pin "1") (pinfunction "1_1") (pintype "passive"))
      (node (ref "C21") (pin "1") (pinfunction "1_1") (pintype "passive"))
      (node (ref "C22") (pin "1") (pinfunction "1_1") (pintype "passive"))
      (node (ref "C23") (pin "1") (pinfunction "1_1") (pintype "passive"))
      (node (ref "C24") (pin "1") (pinfunction "1_1") (pintype "passive"))
      (node (ref "C25") (pin "1") (pinfunction "1_1") (pintype "passive"))
      (node (ref "C26") (pin "1") (pinfunction "1_1") (pintype "passive"))
      (node (ref "C27") (pin "2") (pinfunction "2_2") (pintype "passive"))
      (node (ref "C3") (pin "1") (pinfunction "1_1") (pintype "passive"))
      (node (ref "C4") (pin "1") (pinfunction "1_1") (pintype "passive"))
      (node (ref "C6") (pin "1") (pinfunction "1_1") (pintype "passive"))
      (node (ref "C8") (pin "1") (pinfunction "1_1") (pintype "passive"))
      (node (ref "C9") (pin "1") (pinfunction "1_1") (pintype "passive"))
      (node (ref "D1") (pin "2") (pinfunction "K_2") (pintype "passive"))
      (node (ref "J1") (pin "26") (pinfunction "26_26") (pintype "passive"))
      (node (ref "J1") (pin "27") (pinfunction "27_27") (pintype "passive"))
      (node (ref "J1") (pin "28") (pinfunction "28_28") (pintype "passive"))
      (node (ref "J1") (pin "29") (pinfunction "29_29") (pintype "passive"))
      (node (ref "P1") (pin "2") (pinfunction "2_2") (pintype "passive"))
      (node (ref "P6") (pin "2") (pinfunction "2_2") (pintype "power_in"))
      (node (ref "P6") (pin "2A") (pinfunction "2A_2A") (pintype "power_in"))
      (node (ref "P6") (pin "2B") (pinfunction "2B_2B") (pintype "power_in"))
      (node (ref "R1") (pin "2") (pinfunction "2_2") (pintype "passive"))
      (node (ref "R3") (pin "2") (pinfunction "2_2") (pintype "passive"))
      (node (ref "R6") (pin "2") (pinfunction "2_2") (pintype "passive"))
      (node (ref "S1") (pin "1") (pinfunction "1_1") (pintype "passive"))
      (node (ref "ZET6") (pin "107") (pinfunction "107_107") (pintype "passive"))
      (node (ref "ZET6") (pin "120") (pinfunction "120_120") (pintype "passive"))
      (node (ref "ZET6") (pin "130") (pinfunction "130_130") (pintype "passive"))
      (node (ref "ZET6") (pin "143") (pinfunction "143_143") (pintype "passive"))
      (node (ref "ZET6") (pin "16") (pinfunction "16_16") (pintype "passive"))
      (node (ref "ZET6") (pin "30") (pinfunction "30_30") (pintype "passive"))
      (node (ref "ZET6") (pin "38") (pinfunction "38_38") (pintype "passive"))
      (node (ref "ZET6") (pin "51") (pinfunction "51_51") (pintype "passive"))
      (node (ref "ZET6") (pin "61") (pinfunction "61_61") (pintype "passive"))
      (node (ref "ZET6") (pin "71") (pinfunction "71_71") (pintype "passive"))
      (node (ref "ZET6") (pin "83") (pinfunction "83_83") (pintype "passive"))
      (node (ref "ZET6") (pin "94") (pinfunction "94_94") (pintype "passive"))
      (node (ref "c5") (pin "1") (pinfunction "1_1") (pintype "passive"))
    )
    (net (code "122") (name "Net-(D1-A)") (class "Default")
      (node (ref "D1") (pin "1") (pinfunction "A_1") (pintype "passive"))
      (node (ref "R11") (pin "2") (pinfunction "2_2") (pintype "passive"))
    )
    (net (code "123") (name "Net-(K1-I{slash}O-Pad1)") (class "Default")
      (node (ref "K1") (pin "1") (pinfunction "I/O_1") (pintype "passive"))
      (node (ref "P6") (pin "1") (pinfunction "1_1") (pintype "power_in"))
      (node (ref "P6") (pin "1A") (pinfunction "1A_1A") (pintype "power_in"))
      (node (ref "P6") (pin "1B") (pinfunction "1B_1B") (pintype "power_in"))
    )
    (net (code "124") (name "Net-(P6-Pad3)") (class "Default")
      (node (ref "P6") (pin "3") (pinfunction "3_3") (pintype "power_in"))
      (node (ref "P6") (pin "3A") (pinfunction "3A_3A") (pintype "power_in"))
      (node (ref "P6") (pin "3B") (pinfunction "3B_3B") (pintype "power_in"))
    )
    (net (code "125") (name "VCC") (class "Default")
      (node (ref "*") (pin "3") (pinfunction "VCC_3") (pintype "passive"))
      (node (ref "C9") (pin "2") (pinfunction "2_2") (pintype "passive"))
      (node (ref "J1") (pin "22") (pinfunction "22_22") (pintype "passive"))
      (node (ref "J1") (pin "23") (pinfunction "23_23") (pintype "passive"))
      (node (ref "J1") (pin "24") (pinfunction "24_24") (pintype "passive"))
      (node (ref "J1") (pin "25") (pinfunction "25_25") (pintype "passive"))
      (node (ref "K1") (pin "3") (pinfunction "I/O_3") (pintype "passive"))
      (node (ref "R11") (pin "1") (pinfunction "1_1") (pintype "passive"))
    )
    (net (code "126") (name "unconnected-(K1-I{slash}O2-Pad4)") (class "Default")
      (node (ref "K1") (pin "4") (pinfunction "I/O2_4") (pintype "passive"))
    )
    (net (code "127") (name "unconnected-(K1-I{slash}O2-Pad6)") (class "Default")
      (node (ref "K1") (pin "6") (pinfunction "I/O2_6") (pintype "passive"))
    )
    (net (code "128") (name "unconnected-(K1-TAP1-Pad2)") (class "Default")
      (node (ref "K1") (pin "2") (pinfunction "TAP1_2") (pintype "passive"))
    )
    (net (code "129") (name "unconnected-(K1-TAP2-Pad5)") (class "Default")
      (node (ref "K1") (pin "5") (pinfunction "TAP2_5") (pintype "passive"))
    )
    (net (code "130") (name "unconnected-(ZET6-Pad6)") (class "Default")
      (node (ref "ZET6") (pin "6") (pinfunction "6_6") (pintype "passive+no_connect"))
    )
    (net (code "131") (name "unconnected-(ZET6-Pad106)") (class "Default")
      (node (ref "ZET6") (pin "106") (pinfunction "106_106") (pintype "passive+no_connect"))
    )
  )
)
